# pixel-adapter.net
KiCad netlist of a schematic drawn in EAGLE
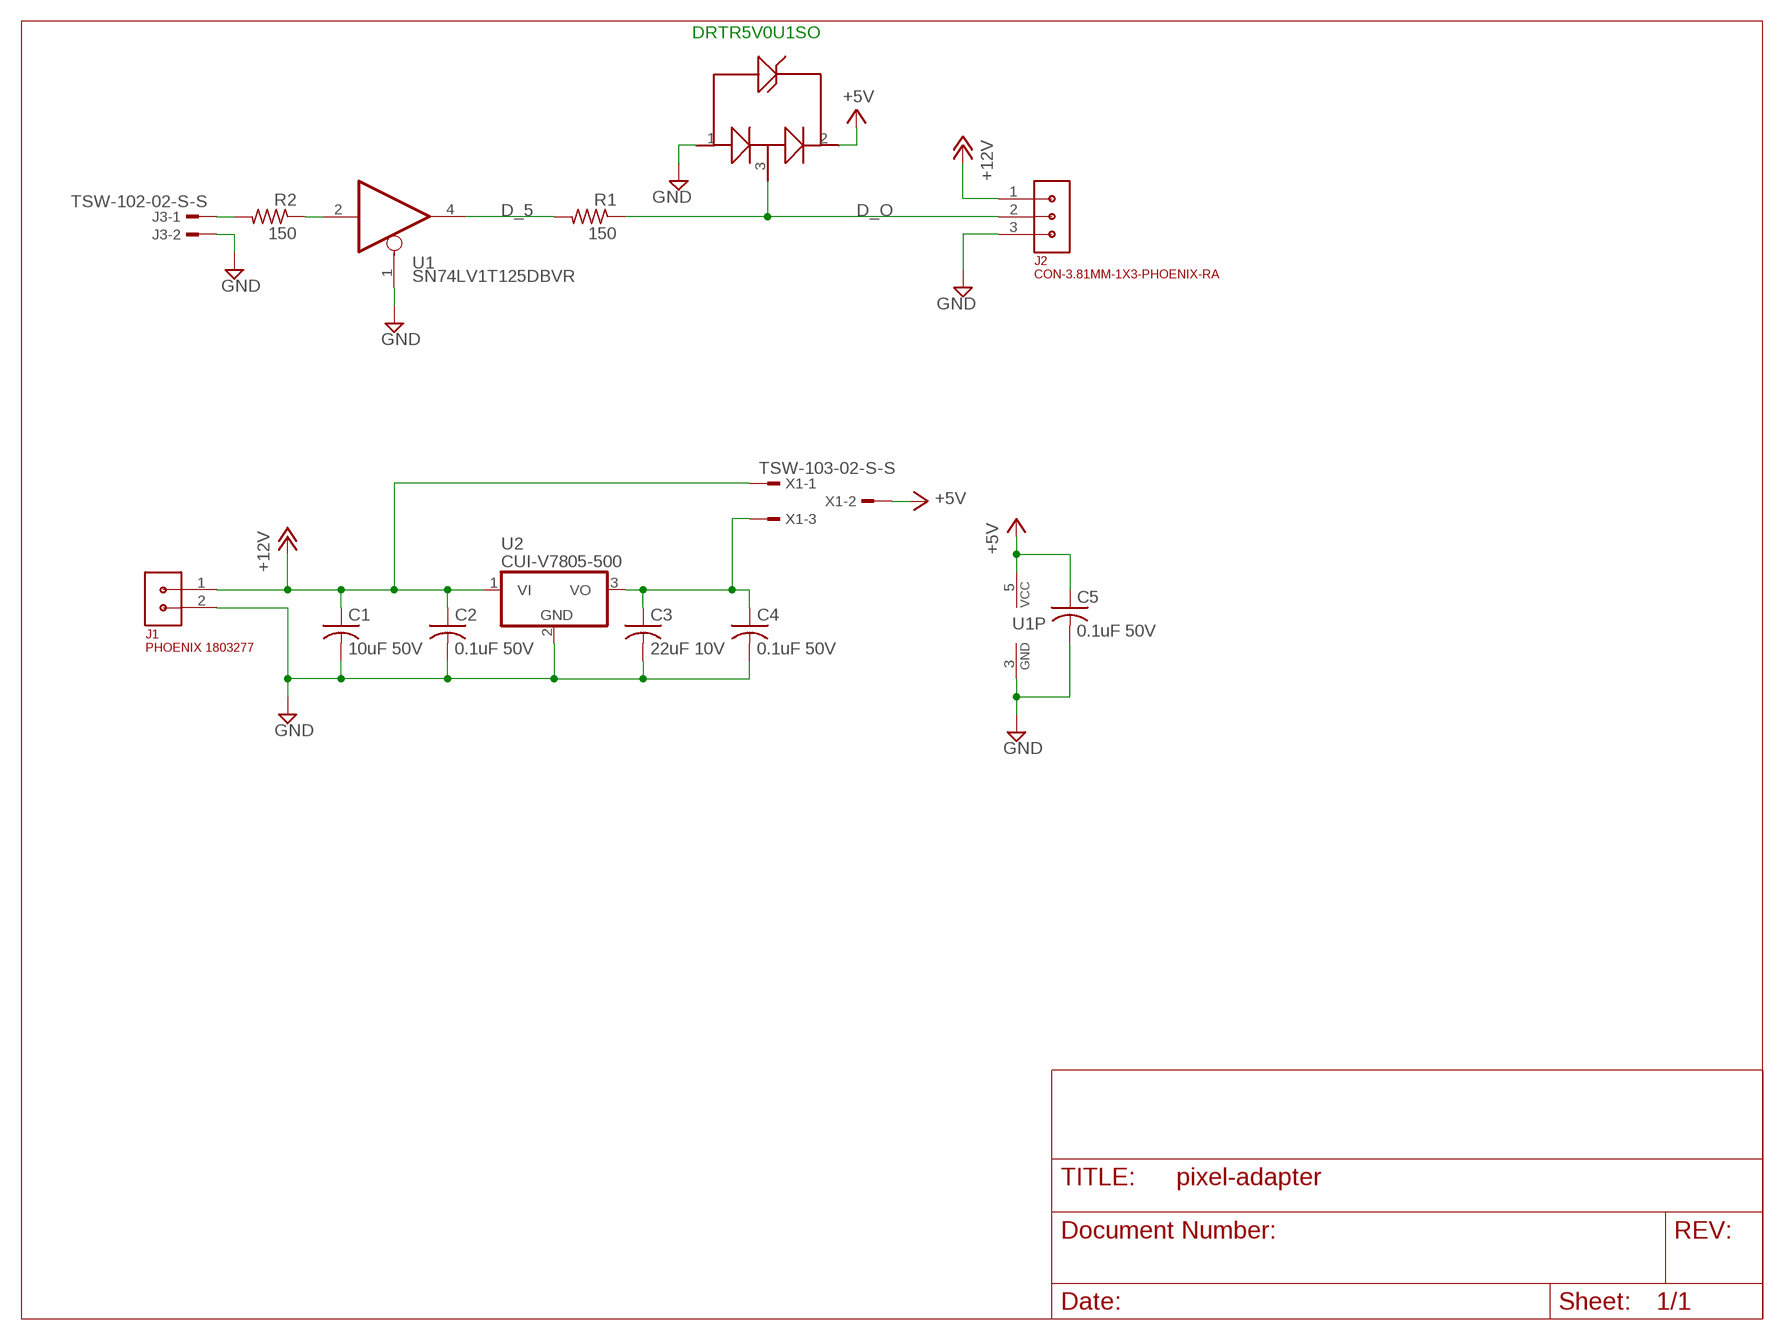
[diagram p0: schematic, sheet 1]

(export (version "E")
  (design (tool "Eeschema 10.0.6"))
  (components
    (comp (ref "C1")
      (value "10uF 50V")
      (footprint "eagle-import:C1210K")
      (fields (field (name "MFR") "KEMET") (field (name "MFR_PART_NO") "C1210C106K5RACTU"))
      (libsource (lib "eagle-import") (part "C-USC1210K"))
    )
    (comp (ref "C2")
      (value "0.1uF 50V")
      (footprint "eagle-import:C1206")
      (fields (field (name "MFR") "KEMET") (field (name "MFR_PART_NO") "C1206S104M5RACTU"))
      (libsource (lib "eagle-import") (part "C-USC1206"))
    )
    (comp (ref "C3")
      (value "22uF 10V")
      (footprint "eagle-import:C1206K")
      (fields (field (name "MFR") "KEMET") (field (name "MFR_PART_NO") "C1206C226K8RAC7800"))
      (libsource (lib "eagle-import") (part "C-USC1206K"))
    )
    (comp (ref "C4")
      (value "0.1uF 50V")
      (footprint "eagle-import:C1206")
      (fields (field (name "MFR") "KEMET") (field (name "MFR_PART_NO") "C1206S104M5RACTU"))
      (libsource (lib "eagle-import") (part "C-USC1206"))
    )
    (comp (ref "C5")
      (value "0.1uF 50V")
      (footprint "eagle-import:C0603K")
      (fields (field (name "MFR") "KEMET") (field (name "MFR_PART_NO") "C1206S104M5RACTU"))
      (libsource (lib "eagle-import") (part "C-USC0603K"))
    )
    (comp (ref "D1")
      (value "DRTR5V0U1SO")
      (footprint "eagle-import:SOT23-3")
      (libsource (lib "eagle-import") (part "DRTR5V0U1SO"))
    )
    (comp (ref "J1")
      (value "PHOENIX 1803277")
      (footprint "eagle-import:CON-PHOENIX-3.81-1X2-RA")
      (libsource (lib "eagle-import") (part "CON-3.81MM-1X2-PHOENIX"))
    )
    (comp (ref "J2")
      (value "CON-3.81MM-1X3-PHOENIX-RA")
      (footprint "eagle-import:CON-PHOENIX-3.81-1X3-RA")
      (libsource (lib "eagle-import") (part "CON-3.81MM-1X3-PHOENIX-RA"))
    )
    (comp (ref "J3")
      (value "TSW-102-02-S-S")
      (footprint "eagle-import:TSW-102-02-S-S")
      (libsource (lib "eagle-import") (part "TSW-102-02-S-S"))
    )
    (comp (ref "R1")
      (value "150")
      (footprint "eagle-import:M1206")
      (libsource (lib "eagle-import") (part "R-US_M1206"))
    )
    (comp (ref "R2")
      (value "150")
      (footprint "eagle-import:M1206")
      (libsource (lib "eagle-import") (part "R-US_M1206"))
    )
    (comp (ref "U1")
      (value "SN74LV1T125DBVR")
      (footprint "eagle-import:SOT23-5")
      (fields (field (name "MFR") "TI") (field (name "MFR_PART_NO") "SN74LV1T125DBVR"))
      (libsource (lib "eagle-import") (part "741G125DBVAHC"))
    )
    (comp (ref "U2")
      (value "CUI-V7805-500")
      (footprint "eagle-import:CUI-78XX-500")
      (libsource (lib "eagle-import") (part "CUI-V7803-500"))
    )
    (comp (ref "X1")
      (value "TSW-103-02-S-S")
      (footprint "eagle-import:TSW-103-02-S-S")
      (libsource (lib "eagle-import") (part "TSW-103-02-S-S"))
    )
  )
  (nets
    (net (code "1") (name "+5V") (class "Default")
      (node (ref "C5") (pin "1") (pinfunction "1_1") (pintype "passive"))
      (node (ref "D1") (pin "2") (pinfunction "2_2") (pintype "bidirectional"))
      (node (ref "U1") (pin "5") (pinfunction "VCC_5") (pintype "power_in"))
      (node (ref "X1") (pin "2") (pinfunction "1_2") (pintype "passive"))
    )
    (net (code "2") (name "+12V") (class "Default")
      (node (ref "C1") (pin "1") (pinfunction "1_1") (pintype "passive"))
      (node (ref "C2") (pin "1") (pinfunction "1_1") (pintype "passive"))
      (node (ref "J1") (pin "1") (pinfunction "1_1") (pintype "bidirectional"))
      (node (ref "J2") (pin "1") (pinfunction "1_1") (pintype "bidirectional"))
      (node (ref "U2") (pin "1") (pinfunction "VI_1") (pintype "input"))
      (node (ref "X1") (pin "1") (pinfunction "1_1") (pintype "passive"))
    )
    (net (code "3") (name "/D_5") (class "Default")
      (node (ref "R1") (pin "2") (pinfunction "2_2") (pintype "passive"))
      (node (ref "U1") (pin "4") (pinfunction "O_4") (pintype "tri_state"))
    )
    (net (code "4") (name "/D_O") (class "Default")
      (node (ref "D1") (pin "3") (pinfunction "1_3") (pintype "bidirectional"))
      (node (ref "J2") (pin "2") (pinfunction "2_2") (pintype "bidirectional"))
      (node (ref "R1") (pin "1") (pinfunction "1_1") (pintype "passive"))
    )
    (net (code "5") (name "GND") (class "Default")
      (node (ref "C1") (pin "2") (pinfunction "2_2") (pintype "passive"))
      (node (ref "C2") (pin "2") (pinfunction "2_2") (pintype "passive"))
      (node (ref "C3") (pin "2") (pinfunction "2_2") (pintype "passive"))
      (node (ref "C4") (pin "2") (pinfunction "2_2") (pintype "passive"))
      (node (ref "C5") (pin "2") (pinfunction "2_2") (pintype "passive"))
      (node (ref "D1") (pin "1") (pinfunction "3_1") (pintype "bidirectional"))
      (node (ref "J1") (pin "2") (pinfunction "2_2") (pintype "bidirectional"))
      (node (ref "J2") (pin "3") (pinfunction "3_3") (pintype "bidirectional"))
      (node (ref "J3") (pin "2") (pinfunction "1_2") (pintype "passive"))
      (node (ref "U1") (pin "1") (pinfunction "OE_1") (pintype "input"))
      (node (ref "U1") (pin "3") (pinfunction "GND_3") (pintype "power_in"))
      (node (ref "U2") (pin "2") (pinfunction "GND_2") (pintype "passive"))
    )
    (net (code "6") (name "Net-(J3-Pad1)") (class "Default")
      (node (ref "J3") (pin "1") (pinfunction "1_1") (pintype "passive"))
      (node (ref "R2") (pin "2") (pinfunction "2_2") (pintype "passive"))
    )
    (net (code "7") (name "Net-(U1A-I)") (class "Default")
      (node (ref "R2") (pin "1") (pinfunction "1_1") (pintype "passive"))
      (node (ref "U1") (pin "2") (pinfunction "I_2") (pintype "input"))
    )
    (net (code "8") (name "Net-(U2-VO)") (class "Default")
      (node (ref "C3") (pin "1") (pinfunction "1_1") (pintype "passive"))
      (node (ref "C4") (pin "1") (pinfunction "1_1") (pintype "passive"))
      (node (ref "U2") (pin "3") (pinfunction "VO_3") (pintype "passive"))
      (node (ref "X1") (pin "3") (pinfunction "1_3") (pintype "passive"))
    )
  )
)
